# BAM_Reference_R2_1.net
KiCad netlist of a schematic drawn in EAGLE
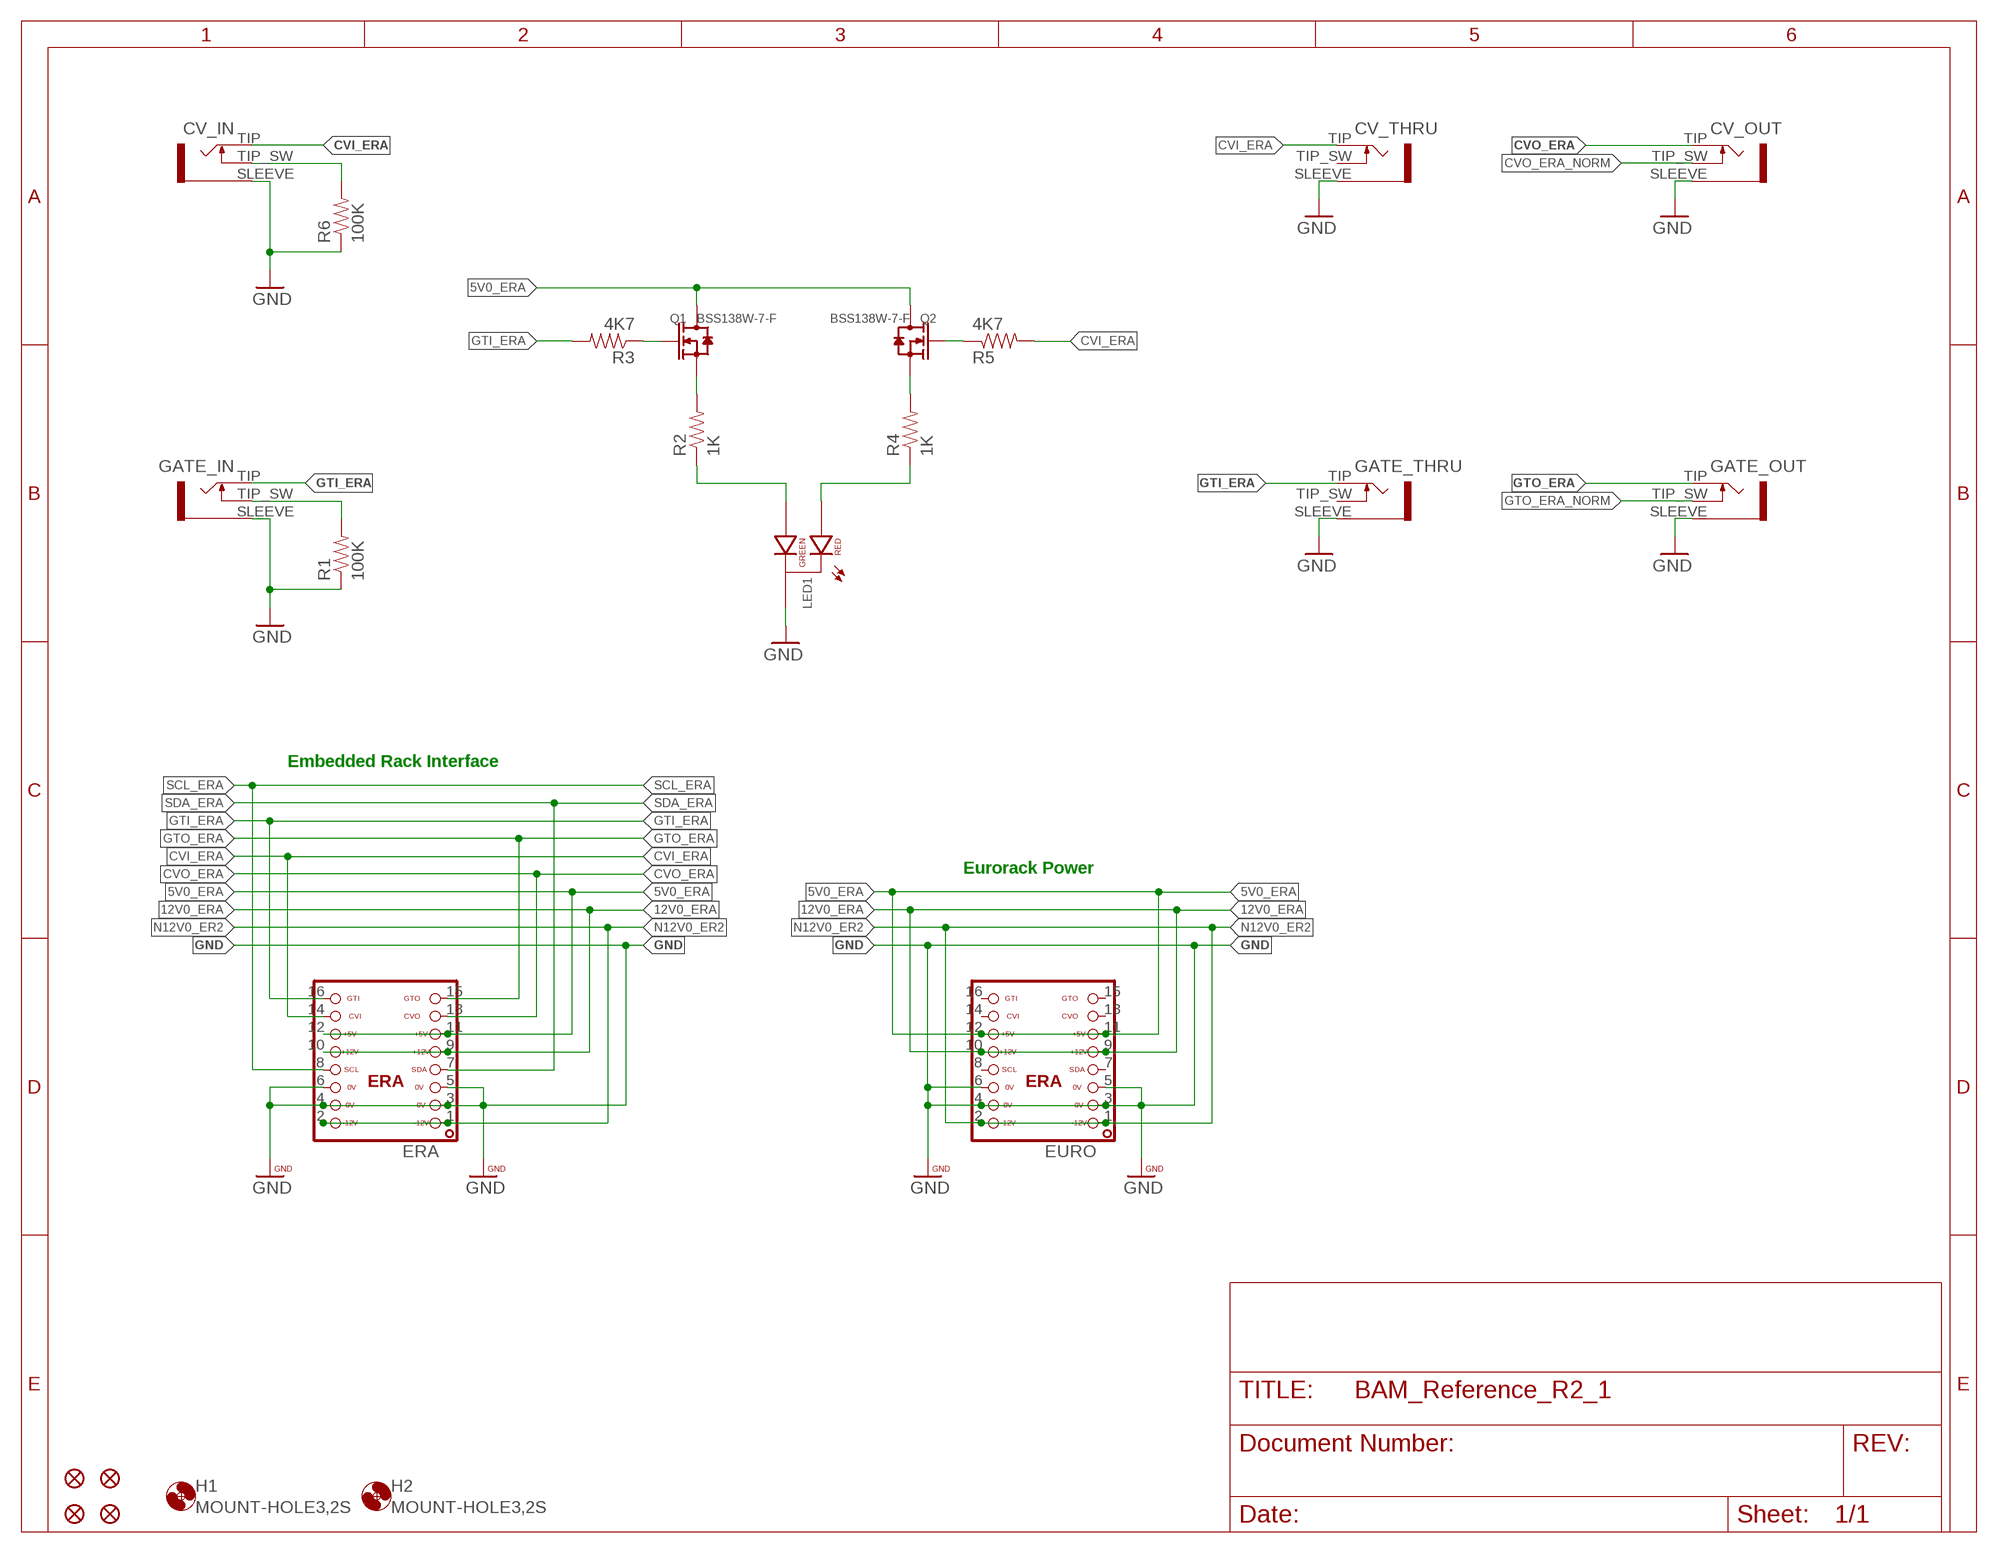
[diagram p0: schematic, sheet 1]

(export (version "E")
  (design (tool "Eeschema 10.0.6"))
  (components
    (comp (ref "CV_IN")
      (value "JACK-3_5MM-MONO-SW-MJ_3502")
      (footprint "eagle-import:MJ-3502")
      (libsource (lib "eagle-import") (part "oXo_Connectors_JACK-3_5MM-MONO-SW-MJ_3502"))
    )
    (comp (ref "CV_OUT")
      (value "JACK-3_5MM-MONO-SW-MJ_3502")
      (footprint "eagle-import:MJ-3502")
      (libsource (lib "eagle-import") (part "JACK-3_5MM-MONO-SW-MJ_3502"))
    )
    (comp (ref "CV_THRU")
      (value "JACK-3_5MM-MONO-SW-MJ_3502")
      (footprint "eagle-import:MJ-3502")
      (libsource (lib "eagle-import") (part "JACK-3_5MM-MONO-SW-MJ_3502"))
    )
    (comp (ref "ERA")
      (value "ERA-SHROUD")
      (footprint "eagle-import:ERA")
      (libsource (lib "eagle-import") (part "ERA-SHROUD"))
    )
    (comp (ref "EURO")
      (value "ERA-SHROUD")
      (footprint "eagle-import:ERA")
      (libsource (lib "eagle-import") (part "ERA-SHROUD"))
    )
    (comp (ref "FID1")
      (value "FIDUCIALUFIDUCIAL")
      (footprint "eagle-import:MICRO-FIDUCIAL")
      (libsource (lib "eagle-import") (part "FIDUCIALUFIDUCIAL"))
    )
    (comp (ref "FID2")
      (value "FIDUCIALUFIDUCIAL")
      (footprint "eagle-import:MICRO-FIDUCIAL")
      (libsource (lib "eagle-import") (part "FIDUCIALUFIDUCIAL"))
    )
    (comp (ref "FID3")
      (value "FIDUCIALUFIDUCIAL")
      (footprint "eagle-import:MICRO-FIDUCIAL")
      (libsource (lib "eagle-import") (part "FIDUCIALUFIDUCIAL"))
    )
    (comp (ref "FID4")
      (value "FIDUCIALUFIDUCIAL")
      (footprint "eagle-import:MICRO-FIDUCIAL")
      (libsource (lib "eagle-import") (part "FIDUCIALUFIDUCIAL"))
    )
    (comp (ref "GATE_IN")
      (value "JACK-3_5MM-MONO-SW-MJ_3502")
      (footprint "eagle-import:MJ-3502")
      (libsource (lib "eagle-import") (part "oXo_Connectors_JACK-3_5MM-MONO-SW-MJ_3502"))
    )
    (comp (ref "GATE_OUT")
      (value "JACK-3_5MM-MONO-SW-MJ_3502")
      (footprint "eagle-import:MJ-3502")
      (libsource (lib "eagle-import") (part "JACK-3_5MM-MONO-SW-MJ_3502"))
    )
    (comp (ref "GATE_THRU")
      (value "JACK-3_5MM-MONO-SW-MJ_3502")
      (footprint "eagle-import:MJ-3502")
      (libsource (lib "eagle-import") (part "JACK-3_5MM-MONO-SW-MJ_3502"))
    )
    (comp (ref "H1")
      (value "MOUNT-HOLE3,2S")
      (footprint "eagle-import:3,2,SMALL")
      (libsource (lib "eagle-import") (part "MOUNT-HOLE3,2S"))
    )
    (comp (ref "H2")
      (value "MOUNT-HOLE3,2S")
      (footprint "eagle-import:3,2,SMALL")
      (libsource (lib "eagle-import") (part "MOUNT-HOLE3,2S"))
    )
    (comp (ref "LED1")
      (value "LED-RG-CC-PTH-G18500")
      (footprint "eagle-import:LED-RG-PANEL")
      (libsource (lib "eagle-import") (part "LED-RG-CC-PTH-G18500"))
    )
    (comp (ref "Q1")
      (value "BSS138W-7-F")
      (footprint "eagle-import:SOT-23")
      (libsource (lib "eagle-import") (part "SMD-MOSFET-N-CH-50V-200MA-BSS138W-7-F(SOT-23)"))
    )
    (comp (ref "Q2")
      (value "BSS138W-7-F")
      (footprint "eagle-import:SOT-23")
      (libsource (lib "eagle-import") (part "SMD-MOSFET-N-CH-50V-200MA-BSS138W-7-F(SOT-23)"))
    )
    (comp (ref "R1")
      (value "100K")
      (footprint "eagle-import:0603-RES")
      (libsource (lib "eagle-import") (part "RESISTOR0603"))
    )
    (comp (ref "R2")
      (value "1K")
      (footprint "eagle-import:0603-RES")
      (libsource (lib "eagle-import") (part "RESISTOR0603"))
    )
    (comp (ref "R3")
      (value "4K7")
      (footprint "eagle-import:0603-RES")
      (libsource (lib "eagle-import") (part "RESISTOR0603"))
    )
    (comp (ref "R4")
      (value "1K")
      (footprint "eagle-import:0603-RES")
      (libsource (lib "eagle-import") (part "RESISTOR0603"))
    )
    (comp (ref "R5")
      (value "4K7")
      (footprint "eagle-import:0603-RES")
      (libsource (lib "eagle-import") (part "RESISTOR0603"))
    )
    (comp (ref "R6")
      (value "100K")
      (footprint "eagle-import:0603-RES")
      (libsource (lib "eagle-import") (part "RESISTOR0603"))
    )
  )
  (nets
    (net (code "1") (name "5V0_ERA") (class "Default")
      (node (ref "ERA") (pin "11") (pinfunction "11_11") (pintype "passive"))
      (node (ref "ERA") (pin "12") (pinfunction "12_12") (pintype "passive"))
      (node (ref "EURO") (pin "11") (pinfunction "11_11") (pintype "passive"))
      (node (ref "EURO") (pin "12") (pinfunction "12_12") (pintype "passive"))
      (node (ref "Q1") (pin "3") (pinfunction "D_3") (pintype "passive"))
      (node (ref "Q2") (pin "3") (pinfunction "D_3") (pintype "passive"))
    )
    (net (code "2") (name "12V0_ERA") (class "Default")
      (node (ref "ERA") (pin "10") (pinfunction "10_10") (pintype "passive"))
      (node (ref "ERA") (pin "9") (pinfunction "9_9") (pintype "passive"))
      (node (ref "EURO") (pin "10") (pinfunction "10_10") (pintype "passive"))
      (node (ref "EURO") (pin "9") (pinfunction "9_9") (pintype "passive"))
    )
    (net (code "3") (name "CVI_ERA") (class "Default")
      (node (ref "CV_IN") (pin "TIP") (pinfunction "TIP_TIP") (pintype "passive"))
      (node (ref "CV_THRU") (pin "TIP") (pinfunction "TIP_TIP") (pintype "passive"))
      (node (ref "ERA") (pin "14") (pinfunction "14_14") (pintype "passive"))
      (node (ref "R5") (pin "2") (pinfunction "2_2") (pintype "passive"))
    )
    (net (code "4") (name "CVO_ERA") (class "Default")
      (node (ref "CV_OUT") (pin "TIP") (pinfunction "TIP_TIP") (pintype "passive"))
      (node (ref "ERA") (pin "13") (pinfunction "13_13") (pintype "passive"))
    )
    (net (code "5") (name "CVO_ERA_NORM") (class "Default")
      (node (ref "CV_OUT") (pin "TIP_SW") (pinfunction "TIP_SW_TIP_SW") (pintype "passive"))
    )
    (net (code "6") (name "GND") (class "Default")
      (node (ref "CV_IN") (pin "SLEEVE") (pinfunction "SLEEVE_SLEEVE") (pintype "passive"))
      (node (ref "CV_OUT") (pin "SLEEVE") (pinfunction "SLEEVE_SLEEVE") (pintype "passive"))
      (node (ref "CV_THRU") (pin "SLEEVE") (pinfunction "SLEEVE_SLEEVE") (pintype "passive"))
      (node (ref "ERA") (pin "3") (pinfunction "3_3") (pintype "passive"))
      (node (ref "ERA") (pin "4") (pinfunction "4_4") (pintype "passive"))
      (node (ref "ERA") (pin "5") (pinfunction "5_5") (pintype "passive"))
      (node (ref "ERA") (pin "6") (pinfunction "6_6") (pintype "passive"))
      (node (ref "EURO") (pin "3") (pinfunction "3_3") (pintype "passive"))
      (node (ref "EURO") (pin "4") (pinfunction "4_4") (pintype "passive"))
      (node (ref "EURO") (pin "5") (pinfunction "5_5") (pintype "passive"))
      (node (ref "EURO") (pin "6") (pinfunction "6_6") (pintype "passive"))
      (node (ref "GATE_IN") (pin "SLEEVE") (pinfunction "SLEEVE_SLEEVE") (pintype "passive"))
      (node (ref "GATE_OUT") (pin "SLEEVE") (pinfunction "SLEEVE_SLEEVE") (pintype "passive"))
      (node (ref "GATE_THRU") (pin "SLEEVE") (pinfunction "SLEEVE_SLEEVE") (pintype "passive"))
      (node (ref "LED1") (pin "CC") (pinfunction "CATHODE_CC") (pintype "bidirectional"))
      (node (ref "R1") (pin "1") (pinfunction "1_1") (pintype "passive"))
      (node (ref "R6") (pin "1") (pinfunction "1_1") (pintype "passive"))
    )
    (net (code "7") (name "GTI_ERA") (class "Default")
      (node (ref "ERA") (pin "16") (pinfunction "16_16") (pintype "passive"))
      (node (ref "GATE_IN") (pin "TIP") (pinfunction "TIP_TIP") (pintype "passive"))
      (node (ref "GATE_THRU") (pin "TIP") (pinfunction "TIP_TIP") (pintype "passive"))
      (node (ref "R3") (pin "2") (pinfunction "2_2") (pintype "passive"))
    )
    (net (code "8") (name "GTO_ERA") (class "Default")
      (node (ref "ERA") (pin "15") (pinfunction "15_15") (pintype "passive"))
      (node (ref "GATE_OUT") (pin "TIP") (pinfunction "TIP_TIP") (pintype "passive"))
    )
    (net (code "9") (name "GTO_ERA_NORM") (class "Default")
      (node (ref "GATE_OUT") (pin "TIP_SW") (pinfunction "TIP_SW_TIP_SW") (pintype "passive"))
    )
    (net (code "10") (name "N12V0_ER2") (class "Default")
      (node (ref "ERA") (pin "1") (pinfunction "1_1") (pintype "passive"))
      (node (ref "ERA") (pin "2") (pinfunction "2_2") (pintype "passive"))
      (node (ref "EURO") (pin "1") (pinfunction "1_1") (pintype "passive"))
      (node (ref "EURO") (pin "2") (pinfunction "2_2") (pintype "passive"))
    )
    (net (code "11") (name "Net-(CV_IN-PadTIP_SW)") (class "Default")
      (node (ref "CV_IN") (pin "TIP_SW") (pinfunction "TIP_SW_TIP_SW") (pintype "passive"))
      (node (ref "R6") (pin "2") (pinfunction "2_2") (pintype "passive"))
    )
    (net (code "12") (name "Net-(GATE_IN-PadTIP_SW)") (class "Default")
      (node (ref "GATE_IN") (pin "TIP_SW") (pinfunction "TIP_SW_TIP_SW") (pintype "passive"))
      (node (ref "R1") (pin "2") (pinfunction "2_2") (pintype "passive"))
    )
    (net (code "13") (name "Net-(LED1-GREEN_CATHODE)") (class "Default")
      (node (ref "LED1") (pin "GREEN") (pinfunction "GREEN_CATHODE_GREEN") (pintype "bidirectional"))
      (node (ref "R2") (pin "1") (pinfunction "1_1") (pintype "passive"))
    )
    (net (code "14") (name "Net-(LED1-RED_CATHODE)") (class "Default")
      (node (ref "LED1") (pin "RED") (pinfunction "RED_CATHODE_RED") (pintype "bidirectional"))
      (node (ref "R4") (pin "1") (pinfunction "1_1") (pintype "passive"))
    )
    (net (code "15") (name "Net-(Q1-G)") (class "Default")
      (node (ref "Q1") (pin "1") (pinfunction "G_1") (pintype "passive"))
      (node (ref "R3") (pin "1") (pinfunction "1_1") (pintype "passive"))
    )
    (net (code "16") (name "Net-(Q1-S)") (class "Default")
      (node (ref "Q1") (pin "2") (pinfunction "S_2") (pintype "passive"))
      (node (ref "R2") (pin "2") (pinfunction "2_2") (pintype "passive"))
    )
    (net (code "17") (name "Net-(Q2-G)") (class "Default")
      (node (ref "Q2") (pin "1") (pinfunction "G_1") (pintype "passive"))
      (node (ref "R5") (pin "1") (pinfunction "1_1") (pintype "passive"))
    )
    (net (code "18") (name "Net-(Q2-S)") (class "Default")
      (node (ref "Q2") (pin "2") (pinfunction "S_2") (pintype "passive"))
      (node (ref "R4") (pin "2") (pinfunction "2_2") (pintype "passive"))
    )
    (net (code "19") (name "SCL_ERA") (class "Default")
      (node (ref "ERA") (pin "8") (pinfunction "8_8") (pintype "passive"))
    )
    (net (code "20") (name "SDA_ERA") (class "Default")
      (node (ref "ERA") (pin "7") (pinfunction "7_7") (pintype "passive"))
    )
    (net (code "21") (name "unconnected-(CV_THRU-PadTIP_SW)") (class "Default")
      (node (ref "CV_THRU") (pin "TIP_SW") (pinfunction "TIP_SW_TIP_SW") (pintype "passive"))
    )
    (net (code "22") (name "unconnected-(EURO-Pad7)") (class "Default")
      (node (ref "EURO") (pin "7") (pinfunction "7_7") (pintype "passive"))
    )
    (net (code "23") (name "unconnected-(EURO-Pad8)") (class "Default")
      (node (ref "EURO") (pin "8") (pinfunction "8_8") (pintype "passive"))
    )
    (net (code "24") (name "unconnected-(EURO-Pad13)") (class "Default")
      (node (ref "EURO") (pin "13") (pinfunction "13_13") (pintype "passive"))
    )
    (net (code "25") (name "unconnected-(EURO-Pad14)") (class "Default")
      (node (ref "EURO") (pin "14") (pinfunction "14_14") (pintype "passive"))
    )
    (net (code "26") (name "unconnected-(EURO-Pad15)") (class "Default")
      (node (ref "EURO") (pin "15") (pinfunction "15_15") (pintype "passive"))
    )
    (net (code "27") (name "unconnected-(EURO-Pad16)") (class "Default")
      (node (ref "EURO") (pin "16") (pinfunction "16_16") (pintype "passive"))
    )
    (net (code "28") (name "unconnected-(GATE_THRU-PadTIP_SW)") (class "Default")
      (node (ref "GATE_THRU") (pin "TIP_SW") (pinfunction "TIP_SW_TIP_SW") (pintype "passive"))
    )
  )
)
